# POWER_SUPPLY_-_Copy.net
KiCad netlist of a schematic drawn in EAGLE
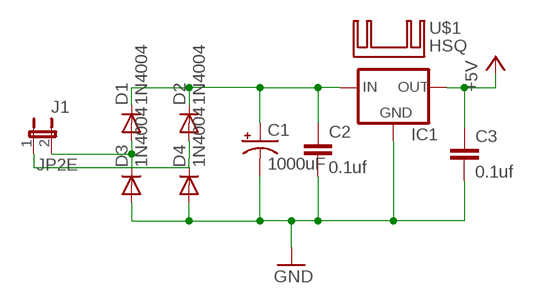
[diagram p0: schematic, sheet 1]

(export (version "E")
  (design (tool "Eeschema 10.0.6"))
  (components
    (comp (ref "C1")
      (value "1000uF")
      (footprint "eagle-import:E3,5-8")
      (libsource (lib "eagle-import") (part "CPOL-USE3.5-8"))
    )
    (comp (ref "C2")
      (value "0.1uf")
      (footprint "eagle-import:C025-024X044")
      (libsource (lib "eagle-import") (part "C-EU025-024X044"))
    )
    (comp (ref "C3")
      (value "0.1uf")
      (footprint "eagle-import:C025-024X044")
      (libsource (lib "eagle-import") (part "C-EU025-024X044"))
    )
    (comp (ref "D1")
      (value "1N4004")
      (footprint "eagle-import:DO41-10")
      (libsource (lib "eagle-import") (part "1N4004"))
    )
    (comp (ref "D2")
      (value "1N4004")
      (footprint "eagle-import:DO41-10")
      (libsource (lib "eagle-import") (part "1N4004"))
    )
    (comp (ref "D3")
      (value "1N4004")
      (footprint "eagle-import:DO41-10")
      (libsource (lib "eagle-import") (part "1N4004"))
    )
    (comp (ref "D4")
      (value "1N4004")
      (footprint "eagle-import:DO41-10")
      (libsource (lib "eagle-import") (part "1N4004"))
    )
    (comp (ref "IC1")
      (value "78XXS")
      (footprint "eagle-import:78XXS")
      (libsource (lib "eagle-import") (part "78XXS"))
    )
    (comp (ref "J1")
      (value "JP2E")
      (footprint "eagle-import:JP2")
      (libsource (lib "eagle-import") (part "JP2E"))
    )
    (comp (ref "U$1")
      (value "HSQ")
      (footprint "eagle-import:HEATSINK")
      (libsource (lib "eagle-import") (part "HSQ"))
    )
  )
  (nets
    (net (code "1") (name "+5V") (class "Default")
      (node (ref "C3") (pin "1") (pinfunction "1_1") (pintype "passive"))
      (node (ref "IC1") (pin "OUT") (pinfunction "OUT_OUT") (pintype "passive"))
    )
    (net (code "2") (name "GND") (class "Default")
      (node (ref "C1") (pin "-") (pinfunction "-_-") (pintype "passive"))
      (node (ref "C2") (pin "2") (pinfunction "2_2") (pintype "passive"))
      (node (ref "C3") (pin "2") (pinfunction "2_2") (pintype "passive"))
      (node (ref "D3") (pin "A") (pinfunction "A_A") (pintype "passive"))
      (node (ref "D4") (pin "A") (pinfunction "A_A") (pintype "passive"))
      (node (ref "IC1") (pin "GND") (pinfunction "GND_GND") (pintype "input"))
    )
    (net (code "3") (name "Net-(C1-Pad+)") (class "Default")
      (node (ref "C1") (pin "+") (pinfunction "+_+") (pintype "passive"))
      (node (ref "C2") (pin "1") (pinfunction "1_1") (pintype "passive"))
      (node (ref "D1") (pin "C") (pinfunction "C_C") (pintype "passive"))
      (node (ref "D2") (pin "C") (pinfunction "C_C") (pintype "passive"))
      (node (ref "IC1") (pin "IN") (pinfunction "IN_IN") (pintype "input"))
    )
    (net (code "4") (name "Net-(D1-PadA)") (class "Default")
      (node (ref "D1") (pin "A") (pinfunction "A_A") (pintype "passive"))
      (node (ref "D3") (pin "C") (pinfunction "C_C") (pintype "passive"))
      (node (ref "J1") (pin "2") (pinfunction "2_2") (pintype "passive"))
    )
    (net (code "5") (name "Net-(D2-PadA)") (class "Default")
      (node (ref "D2") (pin "A") (pinfunction "A_A") (pintype "passive"))
      (node (ref "D4") (pin "C") (pinfunction "C_C") (pintype "passive"))
      (node (ref "J1") (pin "1") (pinfunction "1_1") (pintype "passive"))
    )
  )
)
